# captouch.net
KiCad netlist of a schematic drawn in EAGLE
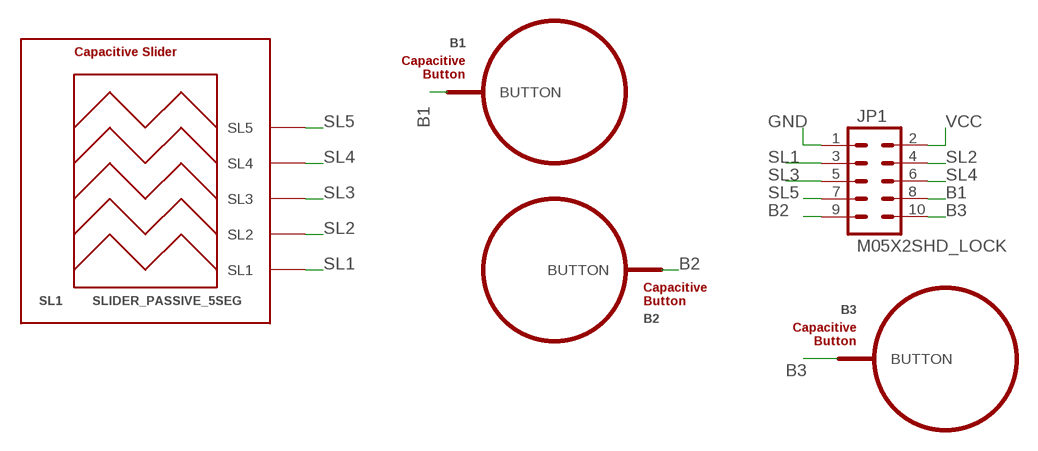
[diagram p0: schematic, sheet 1]

(export (version "E")
  (design (tool "Eeschema 10.0.6"))
  (components
    (comp (ref "B1")
      (value "BUTTON_PASSIVE10MM")
      (footprint "eagle-import:BUTTON_PASSIVE_10MM")
      (libsource (lib "eagle-import") (part "BUTTON_PASSIVE10MM"))
    )
    (comp (ref "B2")
      (value "BUTTON_PASSIVE10MM")
      (footprint "eagle-import:BUTTON_PASSIVE_10MM")
      (libsource (lib "eagle-import") (part "BUTTON_PASSIVE10MM"))
    )
    (comp (ref "B3")
      (value "BUTTON_PASSIVE12MM")
      (footprint "eagle-import:BUTTON_PASSIVE_12MM")
      (libsource (lib "eagle-import") (part "BUTTON_PASSIVE12MM"))
    )
    (comp (ref "JP1")
      (value "M05X2SHD_LOCK")
      (footprint "eagle-import:2X5-SHROUDED_LOCK")
      (libsource (lib "eagle-import") (part "M05X2SHD_LOCK"))
    )
    (comp (ref "SL1")
      (value "SLIDER_PASSIVE_5SEG")
      (footprint "eagle-import:SLIDER_PASSIVE_5SEG_12MM")
      (libsource (lib "eagle-import") (part "SLIDER_PASSIVE_5SEG"))
    )
  )
  (nets
    (net (code "1") (name "/B1") (class "Default")
      (node (ref "B1") (pin "BUTTON") (pinfunction "BUTTON_BUTTON") (pintype "passive"))
      (node (ref "JP1") (pin "8") (pinfunction "8_8") (pintype "passive"))
    )
    (net (code "2") (name "/B2") (class "Default")
      (node (ref "B2") (pin "BUTTON") (pinfunction "BUTTON_BUTTON") (pintype "passive"))
      (node (ref "JP1") (pin "9") (pinfunction "9_9") (pintype "passive"))
    )
    (net (code "3") (name "/B3") (class "Default")
      (node (ref "B3") (pin "BUTTON") (pinfunction "BUTTON_BUTTON") (pintype "passive"))
      (node (ref "JP1") (pin "10") (pinfunction "10_10") (pintype "passive"))
    )
    (net (code "4") (name "/GND") (class "Default")
      (node (ref "JP1") (pin "1") (pinfunction "1_1") (pintype "passive"))
    )
    (net (code "5") (name "/SL1") (class "Default")
      (node (ref "JP1") (pin "3") (pinfunction "3_3") (pintype "passive"))
      (node (ref "SL1") (pin "SL1") (pinfunction "SL1_SL1") (pintype "passive"))
    )
    (net (code "6") (name "/SL2") (class "Default")
      (node (ref "JP1") (pin "4") (pinfunction "4_4") (pintype "passive"))
      (node (ref "SL1") (pin "SL2") (pinfunction "SL2_SL2") (pintype "passive"))
    )
    (net (code "7") (name "/SL3") (class "Default")
      (node (ref "JP1") (pin "5") (pinfunction "5_5") (pintype "passive"))
      (node (ref "SL1") (pin "SL3") (pinfunction "SL3_SL3") (pintype "passive"))
    )
    (net (code "8") (name "/SL4") (class "Default")
      (node (ref "JP1") (pin "6") (pinfunction "6_6") (pintype "passive"))
      (node (ref "SL1") (pin "SL4") (pinfunction "SL4_SL4") (pintype "passive"))
    )
    (net (code "9") (name "/SL5") (class "Default")
      (node (ref "JP1") (pin "7") (pinfunction "7_7") (pintype "passive"))
      (node (ref "SL1") (pin "SL5") (pinfunction "SL5_SL5") (pintype "passive"))
    )
    (net (code "10") (name "/VCC") (class "Default")
      (node (ref "JP1") (pin "2") (pinfunction "2_2") (pintype "passive"))
    )
  )
)
